# watch_dev.net
KiCad netlist of a schematic drawn in EAGLE
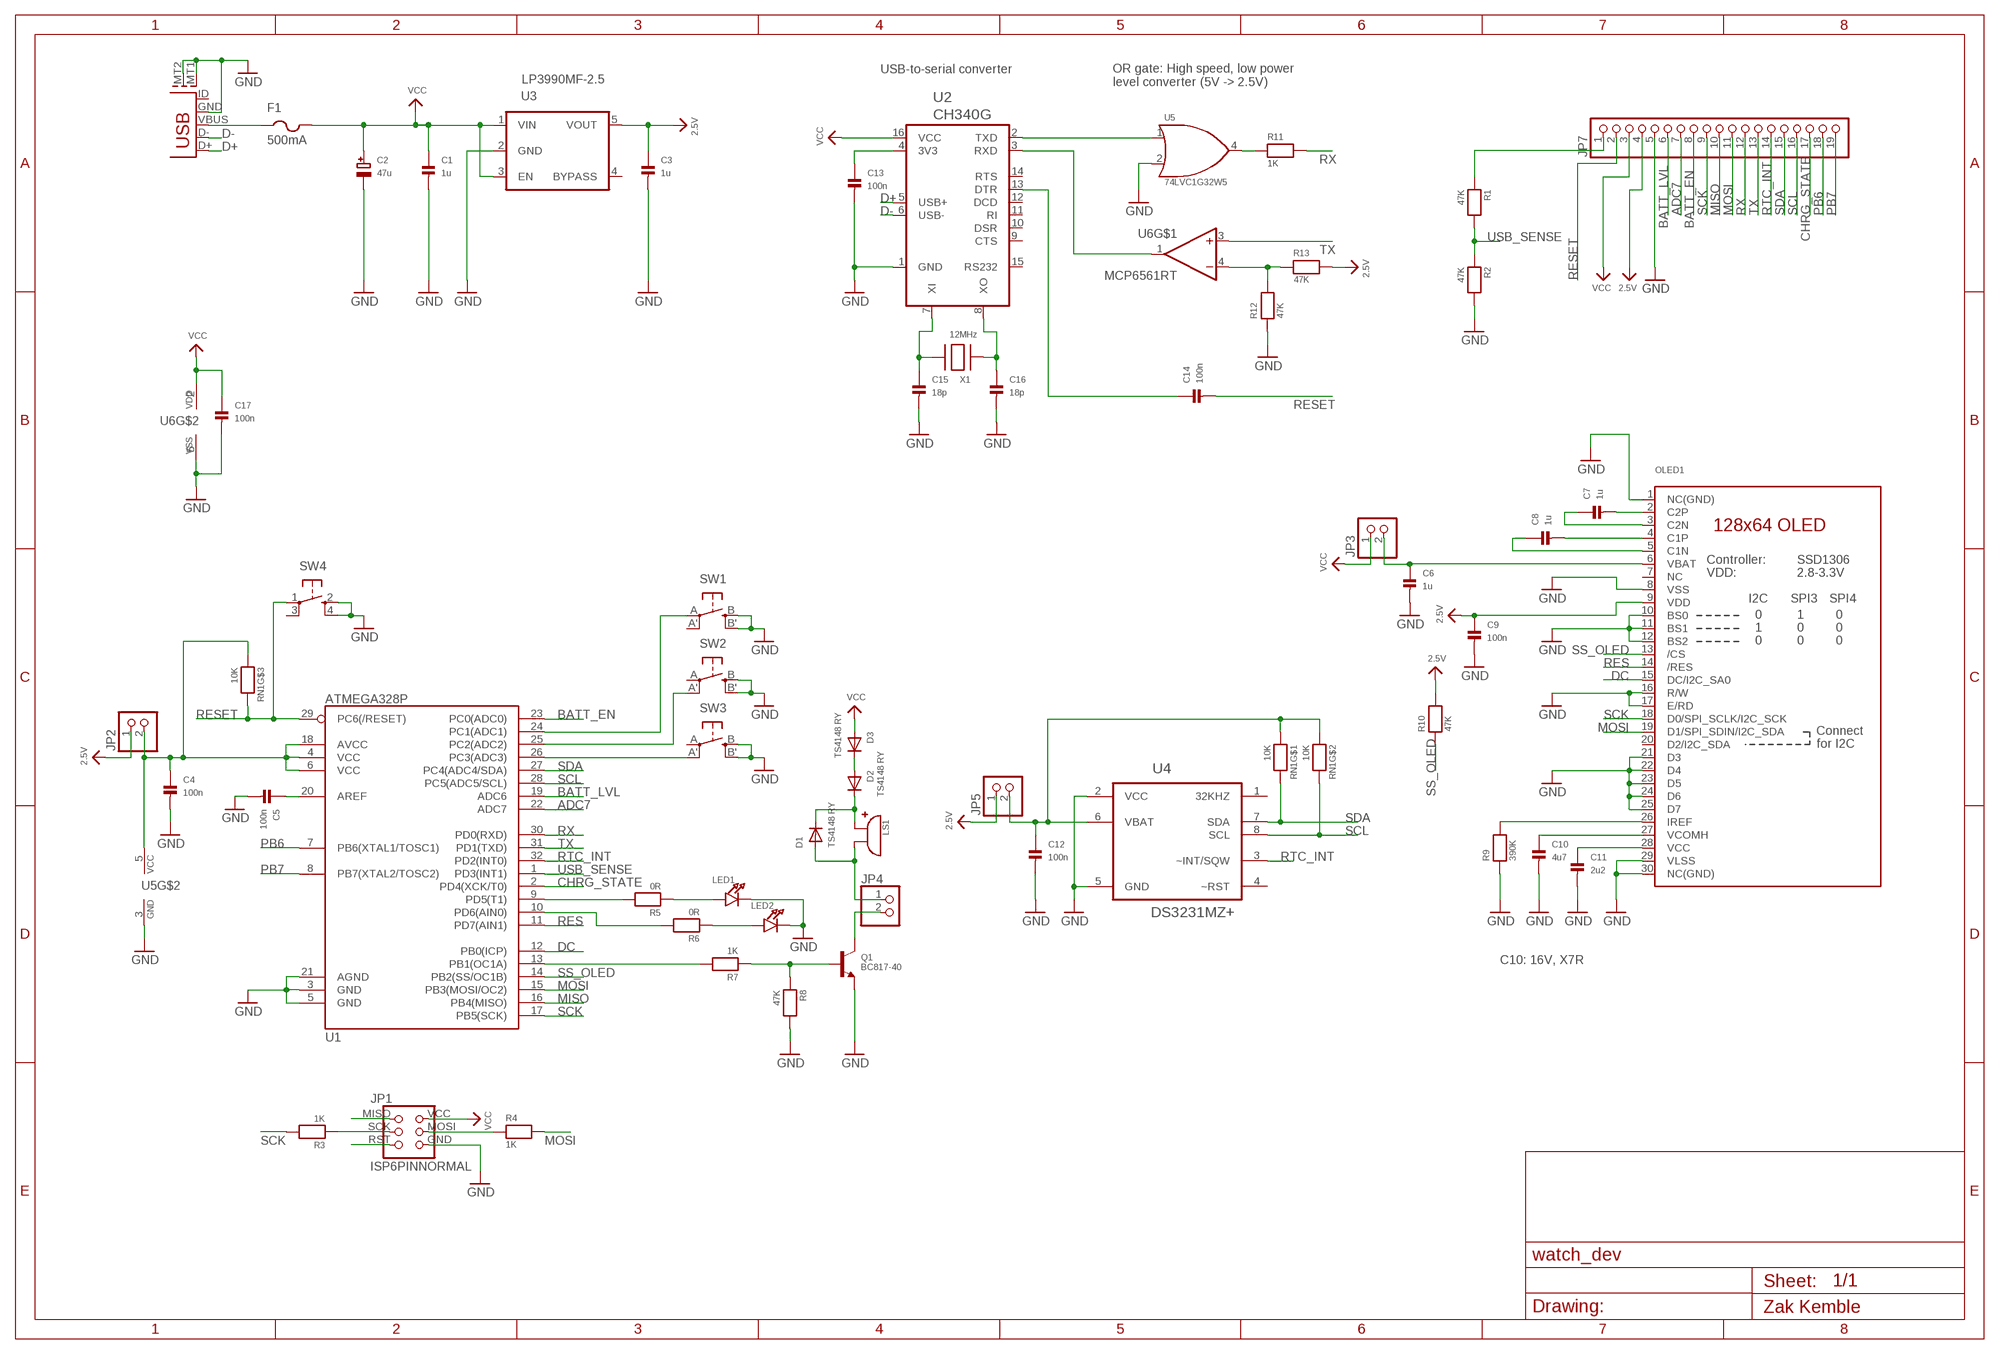
[diagram p0: schematic, sheet 1]

(export (version "E")
  (design (tool "Eeschema 10.0.6"))
  (components
    (comp (ref "C1")
      (value "1u")
      (footprint "eagle-import:0805")
      (libsource (lib "eagle-import") (part "CAP_CERAMIC0805"))
    )
    (comp (ref "C2")
      (value "47u")
      (footprint "eagle-import:PANASONIC_C")
      (libsource (lib "eagle-import") (part "CAP_ELECTROLYTICPANASONIC_C"))
    )
    (comp (ref "C3")
      (value "1u")
      (footprint "eagle-import:0805")
      (libsource (lib "eagle-import") (part "CAP_CERAMIC0805"))
    )
    (comp (ref "C4")
      (value "100n")
      (footprint "eagle-import:0805")
      (libsource (lib "eagle-import") (part "CAP_CERAMIC0805"))
    )
    (comp (ref "C5")
      (value "100n")
      (footprint "eagle-import:0805")
      (libsource (lib "eagle-import") (part "CAP_CERAMIC0805"))
    )
    (comp (ref "C6")
      (value "1u")
      (footprint "eagle-import:0805")
      (libsource (lib "eagle-import") (part "CAP_CERAMIC0805"))
    )
    (comp (ref "C7")
      (value "1u")
      (footprint "eagle-import:0805")
      (libsource (lib "eagle-import") (part "CAP_CERAMIC0805"))
    )
    (comp (ref "C8")
      (value "1u")
      (footprint "eagle-import:0805")
      (libsource (lib "eagle-import") (part "CAP_CERAMIC0805"))
    )
    (comp (ref "C9")
      (value "100n")
      (footprint "eagle-import:0805")
      (libsource (lib "eagle-import") (part "CAP_CERAMIC0805"))
    )
    (comp (ref "C10")
      (value "4u7")
      (footprint "eagle-import:0805")
      (libsource (lib "eagle-import") (part "CAP_CERAMIC0805"))
    )
    (comp (ref "C11")
      (value "2u2")
      (footprint "eagle-import:0805")
      (libsource (lib "eagle-import") (part "CAP_CERAMIC0805"))
    )
    (comp (ref "C12")
      (value "100n")
      (footprint "eagle-import:0805")
      (libsource (lib "eagle-import") (part "CAP_CERAMIC0805"))
    )
    (comp (ref "C13")
      (value "100n")
      (footprint "eagle-import:0805")
      (libsource (lib "eagle-import") (part "CAP_CERAMIC0805"))
    )
    (comp (ref "C14")
      (value "100n")
      (footprint "eagle-import:0805")
      (libsource (lib "eagle-import") (part "CAP_CERAMIC0805"))
    )
    (comp (ref "C15")
      (value "18p")
      (footprint "eagle-import:0805")
      (libsource (lib "eagle-import") (part "CAP_CERAMIC0805"))
    )
    (comp (ref "C16")
      (value "18p")
      (footprint "eagle-import:0805")
      (libsource (lib "eagle-import") (part "CAP_CERAMIC0805"))
    )
    (comp (ref "C17")
      (value "100n")
      (footprint "eagle-import:0805")
      (libsource (lib "eagle-import") (part "CAP_CERAMIC0805"))
    )
    (comp (ref "D1")
      (value "TS4148 RY")
      (footprint "eagle-import:0805_DIODE")
      (libsource (lib "eagle-import") (part "DIODE_08050805"))
    )
    (comp (ref "D2")
      (value "TS4148 RY")
      (footprint "eagle-import:0805_DIODE")
      (libsource (lib "eagle-import") (part "DIODE_08050805"))
    )
    (comp (ref "D3")
      (value "TS4148 RY")
      (footprint "eagle-import:0805_DIODE")
      (libsource (lib "eagle-import") (part "DIODE_08050805"))
    )
    (comp (ref "F1")
      (value "500mA")
      (footprint "eagle-import:1206")
      (libsource (lib "eagle-import") (part "PTCFUSE1206"))
    )
    (comp (ref "JP1")
      (value "ISP6PINNORMAL")
      (footprint "eagle-import:ISP6PIN")
      (libsource (lib "eagle-import") (part "ISP6PINNORMAL"))
    )
    (comp (ref "JP2")
      (value "PINHD-1X2")
      (footprint "eagle-import:1X02")
      (libsource (lib "eagle-import") (part "PINHD-1X2"))
    )
    (comp (ref "JP3")
      (value "PINHD-1X2")
      (footprint "eagle-import:1X02")
      (libsource (lib "eagle-import") (part "PINHD-1X2"))
    )
    (comp (ref "JP4")
      (value "PINHD-1X2")
      (footprint "eagle-import:1X02")
      (libsource (lib "eagle-import") (part "PINHD-1X2"))
    )
    (comp (ref "JP5")
      (value "PINHD-1X2")
      (footprint "eagle-import:1X02")
      (libsource (lib "eagle-import") (part "PINHD-1X2"))
    )
    (comp (ref "JP7")
      (value "PINHD-1X19")
      (footprint "eagle-import:1X19")
      (libsource (lib "eagle-import") (part "PINHD-1X19"))
    )
    (comp (ref "LED1")
      (value "LED0805")
      (footprint "eagle-import:CHIPLED_0805")
      (libsource (lib "eagle-import") (part "LED0805"))
    )
    (comp (ref "LED2")
      (value "LED0805")
      (footprint "eagle-import:CHIPLED_0805")
      (libsource (lib "eagle-import") (part "LED0805"))
    )
    (comp (ref "LS1")
      (value "ABMT-801-RC")
      (footprint "eagle-import:PIEZO")
      (libsource (lib "eagle-import") (part "ABMT-801-RC"))
    )
    (comp (ref "OLED1")
      (value "DISP_OLED_UG-2864HSWEG01_NOOUTLINE")
      (footprint "eagle-import:UG-2864HSWEG01_1.3_WRAPAROUND")
      (libsource (lib "eagle-import") (part "DISP_OLED_UG-2864HSWEG01_NOOUTLINE"))
    )
    (comp (ref "Q1")
      (value "BC817-40")
      (footprint "eagle-import:SOT23-WIDE")
      (libsource (lib "eagle-import") (part "TRANSISTOR_NPNWIDE"))
    )
    (comp (ref "R1")
      (value "47K")
      (footprint "eagle-import:0805")
      (libsource (lib "eagle-import") (part "RESISTOR0805"))
    )
    (comp (ref "R2")
      (value "47K")
      (footprint "eagle-import:0805")
      (libsource (lib "eagle-import") (part "RESISTOR0805"))
    )
    (comp (ref "R3")
      (value "1K")
      (footprint "eagle-import:0805")
      (libsource (lib "eagle-import") (part "RESISTOR0805"))
    )
    (comp (ref "R4")
      (value "1K")
      (footprint "eagle-import:0805")
      (libsource (lib "eagle-import") (part "RESISTOR0805"))
    )
    (comp (ref "R5")
      (value "0R")
      (footprint "eagle-import:0805")
      (libsource (lib "eagle-import") (part "RESISTOR0805"))
    )
    (comp (ref "R6")
      (value "0R")
      (footprint "eagle-import:0805")
      (libsource (lib "eagle-import") (part "RESISTOR0805"))
    )
    (comp (ref "R7")
      (value "1K")
      (footprint "eagle-import:0805")
      (libsource (lib "eagle-import") (part "RESISTOR0805"))
    )
    (comp (ref "R8")
      (value "47K")
      (footprint "eagle-import:0805")
      (libsource (lib "eagle-import") (part "RESISTOR0805"))
    )
    (comp (ref "R9")
      (value "390K")
      (footprint "eagle-import:0805")
      (libsource (lib "eagle-import") (part "RESISTOR0805"))
    )
    (comp (ref "R10")
      (value "47K")
      (footprint "eagle-import:0805")
      (libsource (lib "eagle-import") (part "RESISTOR0805"))
    )
    (comp (ref "R11")
      (value "1K")
      (footprint "eagle-import:0805")
      (libsource (lib "eagle-import") (part "RESISTOR0805"))
    )
    (comp (ref "R12")
      (value "47K")
      (footprint "eagle-import:0805")
      (libsource (lib "eagle-import") (part "RESISTOR0805"))
    )
    (comp (ref "R13")
      (value "47K")
      (footprint "eagle-import:0805")
      (libsource (lib "eagle-import") (part "RESISTOR0805"))
    )
    (comp (ref "RN1")
      (value "10K")
      (footprint "eagle-import:RESPACK_4X0603")
      (libsource (lib "eagle-import") (part "RESISTOR_4PACK"))
    )
    (comp (ref "SW1")
      (value "SPST_TACTMC32882")
      (footprint "eagle-import:TACT_SMD4")
      (libsource (lib "eagle-import") (part "SPST_TACTMC32882"))
    )
    (comp (ref "SW2")
      (value "SPST_TACTMC32882")
      (footprint "eagle-import:TACT_SMD4")
      (libsource (lib "eagle-import") (part "SPST_TACTMC32882"))
    )
    (comp (ref "SW3")
      (value "SPST_TACTMC32882")
      (footprint "eagle-import:TACT_SMD4")
      (libsource (lib "eagle-import") (part "SPST_TACTMC32882"))
    )
    (comp (ref "SW4")
      (value "SPST_TACTKMR2")
      (footprint "eagle-import:KMR2")
      (libsource (lib "eagle-import") (part "SPST_TACTKMR2"))
    )
    (comp (ref "U1")
      (value "ATMEGA328P")
      (footprint "eagle-import:TQFP32-08")
      (libsource (lib "eagle-import") (part "ATMEGA328_SMT"))
    )
    (comp (ref "U2")
      (value "CH340G")
      (footprint "eagle-import:SOIC16_SMPAD")
      (libsource (lib "eagle-import") (part "CH340GSMPAD"))
    )
    (comp (ref "U3")
      (value "LP3990MF-2.5")
      (footprint "eagle-import:SOT95P275X110-5N")
      (libsource (lib "eagle-import") (part "REGULATOR_5"))
    )
    (comp (ref "U4")
      (value "DS3231MZ+")
      (footprint "eagle-import:SOIC8_150MIL_SMPAD")
      (libsource (lib "eagle-import") (part "DS3231MZ+SMPAD"))
    )
    (comp (ref "U5")
      (value "74LVC1G32W5")
      (footprint "eagle-import:SOT95P275X110-5N")
      (libsource (lib "eagle-import") (part "74LVC1G32W5"))
    )
    (comp (ref "U6")
      (value "MCP6561RT")
      (footprint "eagle-import:SOT95P275X110-5N")
      (libsource (lib "eagle-import") (part "OPAMP_SINGLECONFIG2"))
    )
    (comp (ref "USB1")
      (value "USB-MICROBLARGEPAD")
      (footprint "eagle-import:USB-MICROB_LARGEPAD")
      (libsource (lib "eagle-import") (part "USB-MICROBLARGEPAD"))
    )
    (comp (ref "X1")
      (value "12MHz")
      (footprint "eagle-import:NX5032")
      (libsource (lib "eagle-import") (part "XTALNX5032"))
    )
  )
  (nets
    (net (code "1") (name "/ADC7") (class "Default")
      (node (ref "JP7") (pin "7") (pinfunction "7_7") (pintype "passive"))
      (node (ref "U1") (pin "22") (pinfunction "ADC7_22") (pintype "bidirectional"))
    )
    (net (code "2") (name "/BATT_EN") (class "Default")
      (node (ref "JP7") (pin "8") (pinfunction "8_8") (pintype "passive"))
      (node (ref "U1") (pin "23") (pinfunction "PC0(ADC0)_23") (pintype "bidirectional"))
    )
    (net (code "3") (name "/BATT_LVL") (class "Default")
      (node (ref "JP7") (pin "6") (pinfunction "6_6") (pintype "passive"))
      (node (ref "U1") (pin "19") (pinfunction "ADC6_19") (pintype "bidirectional"))
    )
    (net (code "4") (name "/CHRG_STATE") (class "Default")
      (node (ref "JP7") (pin "17") (pinfunction "17_17") (pintype "passive"))
      (node (ref "U1") (pin "2") (pinfunction "PD4(XCK/T0)_2") (pintype "bidirectional"))
    )
    (net (code "5") (name "/D+") (class "Default")
      (node (ref "U2") (pin "5") (pinfunction "USB+_5") (pintype "passive"))
      (node (ref "USB1") (pin "D+") (pinfunction "D+_D+") (pintype "bidirectional"))
    )
    (net (code "6") (name "/D-") (class "Default")
      (node (ref "U2") (pin "6") (pinfunction "USB-_6") (pintype "passive"))
      (node (ref "USB1") (pin "D-") (pinfunction "D-_D-") (pintype "bidirectional"))
    )
    (net (code "7") (name "/DC") (class "Default")
      (node (ref "OLED1") (pin "15") (pinfunction "DC/I2C_SA0_15") (pintype "input"))
      (node (ref "U1") (pin "12") (pinfunction "PB0(ICP)_12") (pintype "bidirectional"))
    )
    (net (code "8") (name "/MISO") (class "Default")
      (node (ref "JP1") (pin "MISO") (pinfunction "1_MISO") (pintype "passive"))
      (node (ref "JP7") (pin "10") (pinfunction "10_10") (pintype "passive"))
      (node (ref "U1") (pin "16") (pinfunction "PB4(MISO)_16") (pintype "bidirectional"))
    )
    (net (code "9") (name "/MOSI") (class "Default")
      (node (ref "JP7") (pin "11") (pinfunction "11_11") (pintype "passive"))
      (node (ref "OLED1") (pin "19") (pinfunction "D1/SPI_SDIN/I2C_SDA_19") (pintype "bidirectional"))
      (node (ref "R4") (pin "2") (pinfunction "2_2") (pintype "passive"))
      (node (ref "U1") (pin "15") (pinfunction "PB3(MOSI/OC2)_15") (pintype "bidirectional"))
    )
    (net (code "10") (name "/PB6") (class "Default")
      (node (ref "JP7") (pin "18") (pinfunction "18_18") (pintype "passive"))
      (node (ref "U1") (pin "7") (pinfunction "PB6(XTAL1/TOSC1)_7") (pintype "bidirectional"))
    )
    (net (code "11") (name "/PB7") (class "Default")
      (node (ref "JP7") (pin "19") (pinfunction "19_19") (pintype "passive"))
      (node (ref "U1") (pin "8") (pinfunction "PB7(XTAL2/TOSC2)_8") (pintype "bidirectional"))
    )
    (net (code "12") (name "/RES") (class "Default")
      (node (ref "OLED1") (pin "14") (pinfunction "/RES_14") (pintype "input"))
      (node (ref "U1") (pin "11") (pinfunction "PD7(AIN1)_11") (pintype "bidirectional"))
    )
    (net (code "13") (name "/RESET") (class "Default")
      (node (ref "C14") (pin "2") (pinfunction "P$2_2") (pintype "passive"))
      (node (ref "JP1") (pin "RST") (pinfunction "5_RST") (pintype "passive"))
      (node (ref "JP7") (pin "2") (pinfunction "2_2") (pintype "passive"))
      (node (ref "RN1") (pin "6") (pinfunction "2_6") (pintype "passive"))
      (node (ref "SW4") (pin "1") (pinfunction "P_1") (pintype "passive"))
      (node (ref "U1") (pin "29") (pinfunction "PC6(/RESET)_29") (pintype "bidirectional"))
    )
    (net (code "14") (name "/RTC_INT") (class "Default")
      (node (ref "JP7") (pin "14") (pinfunction "14_14") (pintype "passive"))
      (node (ref "U1") (pin "32") (pinfunction "PD2(INT0)_32") (pintype "bidirectional"))
      (node (ref "U4") (pin "3") (pinfunction "~{INT/SQW}_3") (pintype "output"))
    )
    (net (code "15") (name "/RX") (class "Default")
      (node (ref "JP7") (pin "12") (pinfunction "12_12") (pintype "passive"))
      (node (ref "R11") (pin "2") (pinfunction "2_2") (pintype "passive"))
      (node (ref "U1") (pin "30") (pinfunction "PD0(RXD)_30") (pintype "bidirectional"))
    )
    (net (code "16") (name "/SCK") (class "Default")
      (node (ref "JP7") (pin "9") (pinfunction "9_9") (pintype "passive"))
      (node (ref "OLED1") (pin "18") (pinfunction "D0/SPI_SCLK/I2C_SCK_18") (pintype "bidirectional"))
      (node (ref "R3") (pin "2") (pinfunction "2_2") (pintype "passive"))
      (node (ref "U1") (pin "17") (pinfunction "PB5(SCK)_17") (pintype "bidirectional"))
    )
    (net (code "17") (name "/SCL") (class "Default")
      (node (ref "JP7") (pin "16") (pinfunction "16_16") (pintype "passive"))
      (node (ref "RN1") (pin "7") (pinfunction "2_7") (pintype "passive"))
      (node (ref "U1") (pin "28") (pinfunction "PC5(ADC5/SCL)_28") (pintype "bidirectional"))
      (node (ref "U4") (pin "8") (pinfunction "SCL_8") (pintype "input"))
    )
    (net (code "18") (name "/SDA") (class "Default")
      (node (ref "JP7") (pin "15") (pinfunction "15_15") (pintype "passive"))
      (node (ref "RN1") (pin "8") (pinfunction "2_8") (pintype "passive"))
      (node (ref "U1") (pin "27") (pinfunction "PC4(ADC4/SDA)_27") (pintype "bidirectional"))
      (node (ref "U4") (pin "7") (pinfunction "SDA_7") (pintype "bidirectional"))
    )
    (net (code "19") (name "/SS_OLED") (class "Default")
      (node (ref "OLED1") (pin "13") (pinfunction "/CS_13") (pintype "input"))
      (node (ref "R10") (pin "1") (pinfunction "1_1") (pintype "passive"))
      (node (ref "U1") (pin "14") (pinfunction "PB2(SS/OC1B)_14") (pintype "bidirectional"))
    )
    (net (code "20") (name "/TX") (class "Default")
      (node (ref "JP7") (pin "13") (pinfunction "13_13") (pintype "passive"))
      (node (ref "U1") (pin "31") (pinfunction "PD1(TXD)_31") (pintype "bidirectional"))
      (node (ref "U6") (pin "3") (pinfunction "+IN_3") (pintype "input"))
    )
    (net (code "21") (name "/USB_SENSE") (class "Default")
      (node (ref "R1") (pin "2") (pinfunction "2_2") (pintype "passive"))
      (node (ref "R2") (pin "1") (pinfunction "1_1") (pintype "passive"))
      (node (ref "U1") (pin "1") (pinfunction "PD3(INT1)_1") (pintype "bidirectional"))
    )
    (net (code "22") (name "2.5V") (class "Default")
      (node (ref "C3") (pin "1") (pinfunction "P$1_1") (pintype "passive"))
      (node (ref "C9") (pin "1") (pinfunction "P$1_1") (pintype "passive"))
      (node (ref "JP2") (pin "1") (pinfunction "1_1") (pintype "passive"))
      (node (ref "JP5") (pin "1") (pinfunction "1_1") (pintype "passive"))
      (node (ref "JP7") (pin "4") (pinfunction "4_4") (pintype "passive"))
      (node (ref "OLED1") (pin "9") (pinfunction "VDD_9") (pintype "power_in"))
      (node (ref "R10") (pin "2") (pinfunction "2_2") (pintype "passive"))
      (node (ref "R13") (pin "2") (pinfunction "2_2") (pintype "passive"))
      (node (ref "U3") (pin "5") (pinfunction "VOUT_5") (pintype "output"))
    )
    (net (code "23") (name "GND") (class "Default")
      (node (ref "C1") (pin "2") (pinfunction "P$2_2") (pintype "passive"))
      (node (ref "C10") (pin "2") (pinfunction "P$2_2") (pintype "passive"))
      (node (ref "C11") (pin "2") (pinfunction "P$2_2") (pintype "passive"))
      (node (ref "C12") (pin "2") (pinfunction "P$2_2") (pintype "passive"))
      (node (ref "C13") (pin "2") (pinfunction "P$2_2") (pintype "passive"))
      (node (ref "C15") (pin "2") (pinfunction "P$2_2") (pintype "passive"))
      (node (ref "C16") (pin "2") (pinfunction "P$2_2") (pintype "passive"))
      (node (ref "C17") (pin "2") (pinfunction "P$2_2") (pintype "passive"))
      (node (ref "C2") (pin "-") (pinfunction "-_-") (pintype "passive"))
      (node (ref "C3") (pin "2") (pinfunction "P$2_2") (pintype "passive"))
      (node (ref "C4") (pin "2") (pinfunction "P$2_2") (pintype "passive"))
      (node (ref "C5") (pin "2") (pinfunction "P$2_2") (pintype "passive"))
      (node (ref "C6") (pin "2") (pinfunction "P$2_2") (pintype "passive"))
      (node (ref "C9") (pin "2") (pinfunction "P$2_2") (pintype "passive"))
      (node (ref "JP1") (pin "GND") (pinfunction "6_GND") (pintype "passive"))
      (node (ref "JP7") (pin "5") (pinfunction "5_5") (pintype "passive"))
      (node (ref "LED1") (pin "C") (pinfunction "C_C") (pintype "passive"))
      (node (ref "LED2") (pin "C") (pinfunction "C_C") (pintype "passive"))
      (node (ref "OLED1") (pin "1") (pinfunction "NC(GND)_1") (pintype "input"))
      (node (ref "OLED1") (pin "10") (pinfunction "BS0_10") (pintype "input"))
      (node (ref "OLED1") (pin "11") (pinfunction "BS1_11") (pintype "input"))
      (node (ref "OLED1") (pin "12") (pinfunction "BS2_12") (pintype "input"))
      (node (ref "OLED1") (pin "16") (pinfunction "R/W_16") (pintype "input"))
      (node (ref "OLED1") (pin "17") (pinfunction "E/RD_17") (pintype "input"))
      (node (ref "OLED1") (pin "21") (pinfunction "D3_21") (pintype "bidirectional"))
      (node (ref "OLED1") (pin "22") (pinfunction "D4_22") (pintype "bidirectional"))
      (node (ref "OLED1") (pin "23") (pinfunction "D5_23") (pintype "bidirectional"))
      (node (ref "OLED1") (pin "24") (pinfunction "D6_24") (pintype "bidirectional"))
      (node (ref "OLED1") (pin "25") (pinfunction "D7_25") (pintype "bidirectional"))
      (node (ref "OLED1") (pin "29") (pinfunction "VLSS_29") (pintype "power_in"))
      (node (ref "OLED1") (pin "30") (pinfunction "NC(GND)_30") (pintype "input"))
      (node (ref "OLED1") (pin "8") (pinfunction "VSS_8") (pintype "power_in"))
      (node (ref "Q1") (pin "2") (pinfunction "E_2") (pintype "passive"))
      (node (ref "R12") (pin "1") (pinfunction "1_1") (pintype "passive"))
      (node (ref "R2") (pin "2") (pinfunction "2_2") (pintype "passive"))
      (node (ref "R8") (pin "2") (pinfunction "2_2") (pintype "passive"))
      (node (ref "R9") (pin "1") (pinfunction "1_1") (pintype "passive"))
      (node (ref "SW1") (pin "B") (pinfunction "S_B") (pintype "passive"))
      (node (ref "SW1") (pin "B'") (pinfunction "S1_B'") (pintype "passive"))
      (node (ref "SW2") (pin "B") (pinfunction "S_B") (pintype "passive"))
      (node (ref "SW2") (pin "B'") (pinfunction "S1_B'") (pintype "passive"))
      (node (ref "SW3") (pin "B") (pinfunction "S_B") (pintype "passive"))
      (node (ref "SW3") (pin "B'") (pinfunction "S1_B'") (pintype "passive"))
      (node (ref "SW4") (pin "2") (pinfunction "S_2") (pintype "passive"))
      (node (ref "SW4") (pin "4") (pinfunction "S1_4") (pintype "passive"))
      (node (ref "U1") (pin "21") (pinfunction "AGND_21") (pintype "bidirectional"))
      (node (ref "U1") (pin "3") (pinfunction "GND_3") (pintype "bidirectional"))
      (node (ref "U1") (pin "5") (pinfunction "GND_5") (pintype "bidirectional"))
      (node (ref "U2") (pin "1") (pinfunction "GND_1") (pintype "passive"))
      (node (ref "U3") (pin "2") (pinfunction "GND_2") (pintype "passive"))
      (node (ref "U4") (pin "2") (pinfunction "VCC_2") (pintype "power_in"))
      (node (ref "U4") (pin "5") (pinfunction "GND_5") (pintype "passive"))
      (node (ref "U5") (pin "2") (pinfunction "B_2") (pintype "input"))
      (node (ref "U5") (pin "3") (pinfunction "GND_3") (pintype "power_in"))
      (node (ref "U6") (pin "5") (pinfunction "VSS_5") (pintype "power_in"))
      (node (ref "USB1") (pin "GND") (pinfunction "GND_GND") (pintype "bidirectional"))
      (node (ref "USB1") (pin "MT1") (pinfunction "SHEILD1_MT1") (pintype "bidirectional"))
      (node (ref "USB1") (pin "MT2") (pinfunction "SHEILD2_MT2") (pintype "bidirectional"))
    )
    (net (code "24") (name "Net-(C4-P$1)") (class "Default")
      (node (ref "C4") (pin "1") (pinfunction "P$1_1") (pintype "passive"))
      (node (ref "JP2") (pin "2") (pinfunction "2_2") (pintype "passive"))
      (node (ref "RN1") (pin "3") (pinfunction "1_3") (pintype "passive"))
      (node (ref "U1") (pin "18") (pinfunction "AVCC_18") (pintype "bidirectional"))
      (node (ref "U1") (pin "4") (pinfunction "VCC_4") (pintype "bidirectional"))
      (node (ref "U1") (pin "6") (pinfunction "VCC_6") (pintype "bidirectional"))
      (node (ref "U5") (pin "5") (pinfunction "VCC_5") (pintype "power_in"))
    )
    (net (code "25") (name "Net-(C5-P$1)") (class "Default")
      (node (ref "C5") (pin "1") (pinfunction "P$1_1") (pintype "passive"))
      (node (ref "U1") (pin "20") (pinfunction "AREF_20") (pintype "bidirectional"))
    )
    (net (code "26") (name "Net-(C6-P$1)") (class "Default")
      (node (ref "C6") (pin "1") (pinfunction "P$1_1") (pintype "passive"))
      (node (ref "JP3") (pin "2") (pinfunction "2_2") (pintype "passive"))
      (node (ref "OLED1") (pin "6") (pinfunction "VBAT_6") (pintype "input"))
    )
    (net (code "27") (name "Net-(C7-P$1)") (class "Default")
      (node (ref "C7") (pin "1") (pinfunction "P$1_1") (pintype "passive"))
      (node (ref "OLED1") (pin "3") (pinfunction "C2N_3") (pintype "input"))
    )
    (net (code "28") (name "Net-(C7-P$2)") (class "Default")
      (node (ref "C7") (pin "2") (pinfunction "P$2_2") (pintype "passive"))
      (node (ref "OLED1") (pin "2") (pinfunction "C2P_2") (pintype "input"))
    )
    (net (code "29") (name "Net-(C8-P$1)") (class "Default")
      (node (ref "C8") (pin "1") (pinfunction "P$1_1") (pintype "passive"))
      (node (ref "OLED1") (pin "5") (pinfunction "C1N_5") (pintype "input"))
    )
    (net (code "30") (name "Net-(C8-P$2)") (class "Default")
      (node (ref "C8") (pin "2") (pinfunction "P$2_2") (pintype "passive"))
      (node (ref "OLED1") (pin "4") (pinfunction "C1P_4") (pintype "input"))
    )
    (net (code "31") (name "Net-(C10-P$1)") (class "Default")
      (node (ref "C10") (pin "1") (pinfunction "P$1_1") (pintype "passive"))
      (node (ref "OLED1") (pin "27") (pinfunction "VCOMH_27") (pintype "output"))
    )
    (net (code "32") (name "Net-(C11-P$1)") (class "Default")
      (node (ref "C11") (pin "1") (pinfunction "P$1_1") (pintype "passive"))
      (node (ref "OLED1") (pin "28") (pinfunction "VCC_28") (pintype "power_in"))
    )
    (net (code "33") (name "Net-(C12-P$1)") (class "Default")
      (node (ref "C12") (pin "1") (pinfunction "P$1_1") (pintype "passive"))
      (node (ref "JP5") (pin "2") (pinfunction "2_2") (pintype "passive"))
      (node (ref "RN1") (pin "1") (pinfunction "1_1") (pintype "passive"))
      (node (ref "RN1") (pin "2") (pinfunction "1_2") (pintype "passive"))
      (node (ref "U4") (pin "6") (pinfunction "VBAT_6") (pintype "power_in"))
    )
    (net (code "34") (name "Net-(C13-P$1)") (class "Default")
      (node (ref "C13") (pin "1") (pinfunction "P$1_1") (pintype "passive"))
      (node (ref "U2") (pin "4") (pinfunction "3V3_4") (pintype "input"))
    )
    (net (code "35") (name "Net-(C14-P$1)") (class "Default")
      (node (ref "C14") (pin "1") (pinfunction "P$1_1") (pintype "passive"))
      (node (ref "U2") (pin "13") (pinfunction "DTR_13") (pintype "output"))
    )
    (net (code "36") (name "Net-(C15-P$1)") (class "Default")
      (node (ref "C15") (pin "1") (pinfunction "P$1_1") (pintype "passive"))
      (node (ref "U2") (pin "7") (pinfunction "XI_7") (pintype "passive"))
      (node (ref "X1") (pin "P$2") (pinfunction "P$2_P$2") (pintype "bidirectional"))
    )
    (net (code "37") (name "Net-(C16-P$1)") (class "Default")
      (node (ref "C16") (pin "1") (pinfunction "P$1_1") (pintype "passive"))
      (node (ref "U2") (pin "8") (pinfunction "XO_8") (pintype "passive"))
      (node (ref "X1") (pin "P$1") (pinfunction "P$1_P$1") (pintype "bidirectional"))
    )
    (net (code "38") (name "Net-(D1-A)") (class "Default")
      (node (ref "D1") (pin "1") (pinfunction "A_1") (pintype "passive"))
      (node (ref "JP4") (pin "1") (pinfunction "1_1") (pintype "passive"))
      (node (ref "LS1") (pin "2") (pinfunction "GND_2") (pintype "passive"))
    )
    (net (code "39") (name "Net-(D1-C)") (class "Default")
      (node (ref "D1") (pin "2") (pinfunction "C_2") (pintype "passive"))
      (node (ref "D2") (pin "2") (pinfunction "C_2") (pintype "passive"))
      (node (ref "LS1") (pin "1") (pinfunction "VCC_1") (pintype "passive"))
    )
    (net (code "40") (name "Net-(D2-A)") (class "Default")
      (node (ref "D2") (pin "1") (pinfunction "A_1") (pintype "passive"))
      (node (ref "D3") (pin "2") (pinfunction "C_2") (pintype "passive"))
    )
    (net (code "41") (name "Net-(F1-Pad1)") (class "Default")
      (node (ref "F1") (pin "1") (pinfunction "1_1") (pintype "passive"))
      (node (ref "USB1") (pin "VBUS") (pinfunction "VBUS_VBUS") (pintype "bidirectional"))
    )
    (net (code "42") (name "Net-(JP1-3)") (class "Default")
      (node (ref "JP1") (pin "SCK") (pinfunction "3_SCK") (pintype "passive"))
      (node (ref "R3") (pin "1") (pinfunction "1_1") (pintype "passive"))
    )
    (net (code "43") (name "Net-(JP1-4)") (class "Default")
      (node (ref "JP1") (pin "MOSI") (pinfunction "4_MOSI") (pintype "passive"))
      (node (ref "R4") (pin "1") (pinfunction "1_1") (pintype "passive"))
    )
    (net (code "44") (name "Net-(JP7-Pad1)") (class "Default")
      (node (ref "JP7") (pin "1") (pinfunction "1_1") (pintype "passive"))
      (node (ref "R1") (pin "1") (pinfunction "1_1") (pintype "passive"))
    )
    (net (code "45") (name "Net-(LED1-PadA)") (class "Default")
      (node (ref "LED1") (pin "A") (pinfunction "A_A") (pintype "passive"))
      (node (ref "R5") (pin "1") (pinfunction "1_1") (pintype "passive"))
    )
    (net (code "46") (name "Net-(LED2-PadA)") (class "Default")
      (node (ref "LED2") (pin "A") (pinfunction "A_A") (pintype "passive"))
      (node (ref "R6") (pin "1") (pinfunction "1_1") (pintype "passive"))
    )
    (net (code "47") (name "Net-(OLED1-IREF)") (class "Default")
      (node (ref "OLED1") (pin "26") (pinfunction "IREF_26") (pintype "input"))
      (node (ref "R9") (pin "2") (pinfunction "2_2") (pintype "passive"))
    )
    (net (code "48") (name "Net-(Q1-B)") (class "Default")
      (node (ref "Q1") (pin "1") (pinfunction "B_1") (pintype "passive"))
      (node (ref "R7") (pin "1") (pinfunction "1_1") (pintype "passive"))
      (node (ref "R8") (pin "1") (pinfunction "1_1") (pintype "passive"))
    )
    (net (code "49") (name "Net-(Q1-C)") (class "Default")
      (node (ref "JP4") (pin "2") (pinfunction "2_2") (pintype "passive"))
      (node (ref "Q1") (pin "3") (pinfunction "C_3") (pintype "passive"))
    )
    (net (code "50") (name "Net-(SW1-P)") (class "Default")
      (node (ref "SW1") (pin "A") (pinfunction "P_A") (pintype "passive"))
      (node (ref "U1") (pin "24") (pinfunction "PC1(ADC1)_24") (pintype "bidirectional"))
    )
    (net (code "51") (name "Net-(SW2-P1)") (class "Default")
      (node (ref "SW2") (pin "A'") (pinfunction "P1_A'") (pintype "passive"))
      (node (ref "U1") (pin "25") (pinfunction "PC2(ADC2)_25") (pintype "bidirectional"))
    )
    (net (code "52") (name "Net-(SW3-P1)") (class "Default")
      (node (ref "SW3") (pin "A'") (pinfunction "P1_A'") (pintype "passive"))
      (node (ref "U1") (pin "26") (pinfunction "PC3(ADC3)_26") (pintype "bidirectional"))
    )
    (net (code "53") (name "Net-(U1-PB1(OC1A))") (class "Default")
      (node (ref "R7") (pin "2") (pinfunction "2_2") (pintype "passive"))
      (node (ref "U1") (pin "13") (pinfunction "PB1(OC1A)_13") (pintype "bidirectional"))
    )
    (net (code "54") (name "Net-(U1-PD5(T1))") (class "Default")
      (node (ref "R5") (pin "2") (pinfunction "2_2") (pintype "passive"))
      (node (ref "U1") (pin "9") (pinfunction "PD5(T1)_9") (pintype "bidirectional"))
    )
    (net (code "55") (name "Net-(U1-PD6(AIN0))") (class "Default")
      (node (ref "R6") (pin "2") (pinfunction "2_2") (pintype "passive"))
      (node (ref "U1") (pin "10") (pinfunction "PD6(AIN0)_10") (pintype "bidirectional"))
    )
    (net (code "56") (name "Net-(U2-RXD)") (class "Default")
      (node (ref "U2") (pin "3") (pinfunction "RXD_3") (pintype "output"))
      (node (ref "U6") (pin "1") (pinfunction "OUT_1") (pintype "output"))
    )
    (net (code "57") (name "Net-(U2-TXD)") (class "Default")
      (node (ref "U2") (pin "2") (pinfunction "TXD_2") (pintype "output"))
      (node (ref "U5") (pin "1") (pinfunction "A_1") (pintype "input"))
    )
    (net (code "58") (name "Net-(U5A-Y)") (class "Default")
      (node (ref "R11") (pin "1") (pinfunction "1_1") (pintype "passive"))
      (node (ref "U5") (pin "4") (pinfunction "Y_4") (pintype "output"))
    )
    (net (code "59") (name "Net-(U6A--IN)") (class "Default")
      (node (ref "R12") (pin "2") (pinfunction "2_2") (pintype "passive"))
      (node (ref "R13") (pin "1") (pinfunction "1_1") (pintype "passive"))
      (node (ref "U6") (pin "4") (pinfunction "-IN_4") (pintype "input"))
    )
    (net (code "60") (name "VCC") (class "Default")
      (node (ref "C1") (pin "1") (pinfunction "P$1_1") (pintype "passive"))
      (node (ref "C17") (pin "1") (pinfunction "P$1_1") (pintype "passive"))
      (node (ref "C2") (pin "+") (pinfunction "+_+") (pintype "passive"))
      (node (ref "D3") (pin "1") (pinfunction "A_1") (pintype "passive"))
      (node (ref "F1") (pin "2") (pinfunction "2_2") (pintype "passive"))
      (node (ref "JP1") (pin "VCC") (pinfunction "2_VCC") (pintype "power_in"))
      (node (ref "JP3") (pin "1") (pinfunction "1_1") (pintype "passive"))
      (node (ref "JP7") (pin "3") (pinfunction "3_3") (pintype "passive"))
      (node (ref "U2") (pin "16") (pinfunction "VCC_16") (pintype "passive"))
      (node (ref "U3") (pin "1") (pinfunction "VIN_1") (pintype "power_in"))
      (node (ref "U3") (pin "3") (pinfunction "EN_3") (pintype "input"))
      (node (ref "U6") (pin "2") (pinfunction "VDD_2") (pintype "power_in"))
    )
    (net (code "61") (name "unconnected-(OLED1-D2{slash}I2C_SDA-Pad20)") (class "Default")
      (node (ref "OLED1") (pin "20") (pinfunction "D2/I2C_SDA_20") (pintype "bidirectional"))
    )
    (net (code "62") (name "unconnected-(OLED1-NC-Pad7)") (class "Default")
      (node (ref "OLED1") (pin "7") (pinfunction "NC_7") (pintype "no_connect"))
    )
    (net (code "63") (name "unconnected-(SW1-P1-PadA')") (class "Default")
      (node (ref "SW1") (pin "A'") (pinfunction "P1_A'") (pintype "passive"))
    )
    (net (code "64") (name "unconnected-(SW2-P-PadA)") (class "Default")
      (node (ref "SW2") (pin "A") (pinfunction "P_A") (pintype "passive"))
    )
    (net (code "65") (name "unconnected-(SW3-P-PadA)") (class "Default")
      (node (ref "SW3") (pin "A") (pinfunction "P_A") (pintype "passive"))
    )
    (net (code "66") (name "unconnected-(SW4-P1-Pad3)") (class "Default")
      (node (ref "SW4") (pin "3") (pinfunction "P1_3") (pintype "passive"))
    )
    (net (code "67") (name "unconnected-(U2-CTS-Pad9)") (class "Default")
      (node (ref "U2") (pin "9") (pinfunction "CTS_9") (pintype "output"))
    )
    (net (code "68") (name "unconnected-(U2-DCD-Pad12)") (class "Default")
      (node (ref "U2") (pin "12") (pinfunction "DCD_12") (pintype "output"))
    )
    (net (code "69") (name "unconnected-(U2-DSR-Pad10)") (class "Default")
      (node (ref "U2") (pin "10") (pinfunction "DSR_10") (pintype "output"))
    )
    (net (code "70") (name "unconnected-(U2-RI-Pad11)") (class "Default")
      (node (ref "U2") (pin "11") (pinfunction "RI_11") (pintype "output"))
    )
    (net (code "71") (name "unconnected-(U2-RS232-Pad15)") (class "Default")
      (node (ref "U2") (pin "15") (pinfunction "RS232_15") (pintype "output"))
    )
    (net (code "72") (name "unconnected-(U2-RTS-Pad14)") (class "Default")
      (node (ref "U2") (pin "14") (pinfunction "RTS_14") (pintype "output"))
    )
    (net (code "73") (name "unconnected-(U3-BYPASS-Pad4)") (class "Default")
      (node (ref "U3") (pin "4") (pinfunction "BYPASS_4") (pintype "passive"))
    )
    (net (code "74") (name "unconnected-(U4-32KHZ-Pad1)") (class "Default")
      (node (ref "U4") (pin "1") (pinfunction "32KHZ_1") (pintype "output"))
    )
    (net (code "75") (name "unconnected-(U4-~{RST}-Pad4)") (class "Default")
      (node (ref "U4") (pin "4") (pinfunction "~{RST}_4") (pintype "bidirectional"))
    )
    (net (code "76") (name "unconnected-(USB1-PadID)") (class "Default")
      (node (ref "USB1") (pin "ID") (pinfunction "ID_ID") (pintype "bidirectional"))
    )
  )
)
